# power.net
KiCad netlist of a schematic drawn in Altium Designer
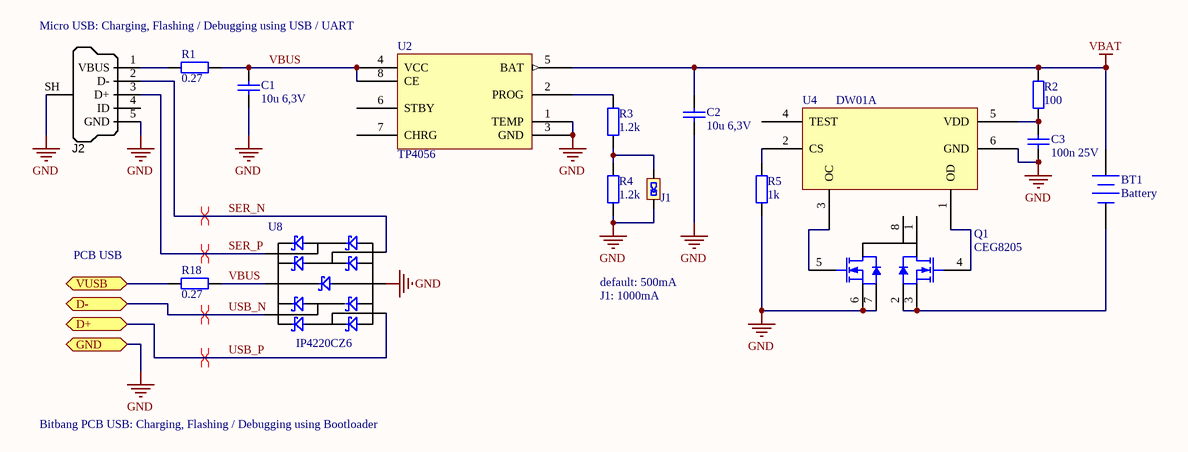
[diagram p0: power.SchDoc]

(export (version "E")
  (design (tool "Eeschema 10.0.6"))
  (components
    (comp (ref "BT1")
      (value "Battery")
      (footprint "BAT-2")
      (description "Multicell Battery")
      (fields (field (name "PUBLISHER") "Altium Limited"))
      (libsource (lib "Miscellaneous Devices") (part "Battery"))
    )
    (comp (ref "C1")
      (value "10u 6,3V")
      (footprint "C-0603-H")
      (description "Capacitor 10uF 6,3V")
      (libsource (lib "Passives") (part "C-0603-10u-6,3V"))
    )
    (comp (ref "C2")
      (value "10u 6,3V")
      (footprint "C-0603-H")
      (description "Capacitor 10uF 6,3V")
      (libsource (lib "Passives") (part "C-0603-10u-6,3V"))
    )
    (comp (ref "C3")
      (value "100n 25V")
      (footprint "C-0603-M")
      (description "Capacitor 100n 25V")
      (libsource (lib "Passives") (part "C-0603-100n-25V"))
    )
    (comp (ref "J1")
      (value "jumper")
      (footprint "JUMPER 1-1")
      (libsource (lib "advanced") (part "jumper 1-1"))
    )
    (comp (ref "J2")
      (value "USB Micro Type B (recommended if hand soldering)")
      (footprint "USB_Micro-B_FCI_SMD")
      (description "Connector SMD-THD USB Micro Type B middle mount")
      (libsource (lib "PBL - Connectors") (part "USB_Micro_TypeB_FCI"))
    )
    (comp (ref "Q1")
      (value "CEG8205")
      (footprint "TSSOP8")
      (description "Dual mini mosfet 20V 4.5A")
      (libsource (lib "advanced") (part "MOSFET-CEG8205"))
    )
    (comp (ref "R1")
      (value "0.27")
      (footprint "R-1206-M")
      (description "Resistor 0.27")
      (libsource (lib "Passives") (part "R-1206-0R27"))
    )
    (comp (ref "R2")
      (value "100")
      (footprint "R-0603-M")
      (description "Resistor 100")
      (libsource (lib "Passives") (part "R-0603-100"))
    )
    (comp (ref "R3")
      (value "1.2k")
      (footprint "R-0603-M")
      (description "Resistor 1.2k")
      (libsource (lib "Passives") (part "R-0603-1k2"))
    )
    (comp (ref "R4")
      (value "1.2k")
      (footprint "R-0603-M")
      (description "Resistor 1.2k")
      (libsource (lib "Passives") (part "R-0603-1k2"))
    )
    (comp (ref "R5")
      (value "1k")
      (footprint "R-0603-M")
      (description "Resistor 1k")
      (libsource (lib "Passives") (part "R-0603-1k"))
    )
    (comp (ref "R18")
      (value "0.27")
      (footprint "R-1206-M")
      (description "Resistor 0.27")
      (libsource (lib "Passives") (part "R-1206-0R27"))
    )
    (comp (ref "U2")
      (value "TP4056")
      (footprint "SOIC127P600X20_HS-9N")
      (description "1A standalone linear charging IC")
      (libsource (lib "advanced") (part "TP4056"))
    )
    (comp (ref "U4")
      (value "DW01A")
      (footprint "SOT23-6")
      (description "Single Cell LiIon LiPo Protection")
      (libsource (lib "advanced") (part "DW01A"))
    )
    (comp (ref "U8")
      (value "IP4220CZ6")
      (footprint "SOT23-6")
      (description "USB ESD Protection")
      (libsource (lib "advanced") (part "IP4220CZ6"))
    )
  )
  (nets
    (net (code "1") (name "/SER_N") (class "Default")
      (node (ref "J2") (pin "2") (pinfunction "D-_2") (pintype "passive"))
      (node (ref "U8") (pin "3") (pinfunction "bla4_3") (pintype "passive"))
    )
    (net (code "2") (name "/SER_P") (class "Default")
      (node (ref "J2") (pin "3") (pinfunction "D+_3") (pintype "passive"))
      (node (ref "U8") (pin "4") (pinfunction "bla2_4") (pintype "passive"))
    )
    (net (code "3") (name "/USB_N") (class "Default")
      (node (ref "U8") (pin "6") (pinfunction "bla1_6") (pintype "passive"))
    )
    (net (code "4") (name "/USB_P") (class "Default")
      (node (ref "U8") (pin "1") (pinfunction "bla3_1") (pintype "passive"))
    )
    (net (code "5") (name "/VBUS") (class "Default")
      (node (ref "C1") (pin "2") (pinfunction "2_2") (pintype "passive"))
      (node (ref "R1") (pin "2") (pinfunction "2_2") (pintype "passive"))
      (node (ref "R18") (pin "2") (pinfunction "2_2") (pintype "passive"))
      (node (ref "U2") (pin "4") (pinfunction "VCC_4") (pintype "passive"))
      (node (ref "U2") (pin "8") (pinfunction "CE_8") (pintype "passive"))
      (node (ref "U8") (pin "5") (pinfunction "VBUS_5") (pintype "passive"))
    )
    (net (code "6") (name "/VUSB") (class "Default")
      (node (ref "R18") (pin "1") (pinfunction "1_1") (pintype "passive"))
    )
    (net (code "7") (name "GND") (class "Default")
      (node (ref "C1") (pin "1") (pinfunction "1_1") (pintype "passive"))
      (node (ref "C2") (pin "1") (pinfunction "1_1") (pintype "passive"))
      (node (ref "C3") (pin "1") (pinfunction "1_1") (pintype "passive"))
      (node (ref "J1") (pin "2") (pintype "passive"))
      (node (ref "J2") (pin "5") (pinfunction "GND_5") (pintype "passive"))
      (node (ref "J2") (pin "SH") (pinfunction "Shell_SH") (pintype "passive"))
      (node (ref "Q1") (pin "6") (pinfunction "S2_6") (pintype "passive"))
      (node (ref "Q1") (pin "7") (pinfunction "S2_7") (pintype "passive"))
      (node (ref "R4") (pin "1") (pinfunction "1_1") (pintype "passive"))
      (node (ref "R5") (pin "1") (pinfunction "1_1") (pintype "passive"))
      (node (ref "U2") (pin "1") (pinfunction "TEMP_1") (pintype "passive"))
      (node (ref "U2") (pin "3") (pinfunction "GND_3") (pintype "power_in"))
      (node (ref "U4") (pin "6") (pinfunction "GND_6") (pintype "passive"))
      (node (ref "U8") (pin "2") (pinfunction "GND_2") (pintype "passive"))
    )
    (net (code "8") (name "Net-(BT1--)") (class "Default")
      (node (ref "BT1") (pin "2") (pinfunction "-_2") (pintype "passive"))
      (node (ref "Q1") (pin "2") (pinfunction "S1_2") (pintype "passive"))
      (node (ref "Q1") (pin "3") (pinfunction "S1_3") (pintype "passive"))
    )
    (net (code "9") (name "Net-(J1-Pad1)") (class "Default")
      (node (ref "J1") (pin "1") (pintype "passive"))
      (node (ref "R3") (pin "1") (pinfunction "1_1") (pintype "passive"))
      (node (ref "R4") (pin "2") (pinfunction "2_2") (pintype "passive"))
    )
    (net (code "10") (name "Net-(J2-VBUS)") (class "Default")
      (node (ref "J2") (pin "1") (pinfunction "VBUS_1") (pintype "passive"))
      (node (ref "R1") (pin "1") (pinfunction "1_1") (pintype "passive"))
    )
    (net (code "11") (name "Net-(Q1-G1)") (class "Default")
      (node (ref "Q1") (pin "4") (pinfunction "G1_4") (pintype "passive"))
      (node (ref "U4") (pin "1") (pinfunction "OD_1") (pintype "passive"))
    )
    (net (code "12") (name "Net-(Q1-G2)") (class "Default")
      (node (ref "Q1") (pin "5") (pinfunction "G2_5") (pintype "passive"))
      (node (ref "U4") (pin "3") (pinfunction "OC_3") (pintype "passive"))
    )
    (net (code "13") (name "Net-(U2-PROG)") (class "Default")
      (node (ref "R3") (pin "2") (pinfunction "2_2") (pintype "passive"))
      (node (ref "U2") (pin "2") (pinfunction "PROG_2") (pintype "passive"))
    )
    (net (code "14") (name "Net-(U4-CS)") (class "Default")
      (node (ref "R5") (pin "2") (pinfunction "2_2") (pintype "passive"))
      (node (ref "U4") (pin "2") (pinfunction "CS_2") (pintype "passive"))
    )
    (net (code "15") (name "Net-(U4-VDD)") (class "Default")
      (node (ref "C3") (pin "2") (pinfunction "2_2") (pintype "passive"))
      (node (ref "R2") (pin "1") (pinfunction "1_1") (pintype "passive"))
      (node (ref "U4") (pin "5") (pinfunction "VDD_5") (pintype "passive"))
    )
    (net (code "16") (name "VBAT") (class "Default")
      (node (ref "BT1") (pin "1") (pinfunction "+_1") (pintype "passive"))
      (node (ref "C2") (pin "2") (pinfunction "2_2") (pintype "passive"))
      (node (ref "R2") (pin "2") (pinfunction "2_2") (pintype "passive"))
      (node (ref "U2") (pin "5") (pinfunction "BAT_5") (pintype "output"))
    )
    (net (code "17") (name "unconnected-(J2-ID-Pad4)") (class "Default")
      (node (ref "J2") (pin "4") (pinfunction "ID_4") (pintype "passive"))
    )
    (net (code "18") (name "unconnected-(Q1-D-Pad8)") (class "Default")
      (node (ref "Q1") (pin "8") (pinfunction "D_8") (pintype "passive"))
    )
    (net (code "19") (name "unconnected-(Q1-S-Pad1)") (class "Default")
      (node (ref "Q1") (pin "1") (pinfunction "S_1") (pintype "passive"))
    )
    (net (code "20") (name "unconnected-(U2-CHRG-Pad7)") (class "Default")
      (node (ref "U2") (pin "7") (pinfunction "CHRG_7") (pintype "passive"))
    )
    (net (code "21") (name "unconnected-(U2-STBY-Pad6)") (class "Default")
      (node (ref "U2") (pin "6") (pinfunction "STBY_6") (pintype "passive"))
    )
    (net (code "22") (name "unconnected-(U4-TEST-Pad4)") (class "Default")
      (node (ref "U4") (pin "4") (pinfunction "TEST_4") (pintype "passive"))
    )
  )
)
